# LT3083.net
KiCad netlist of a schematic drawn in Altium Designer
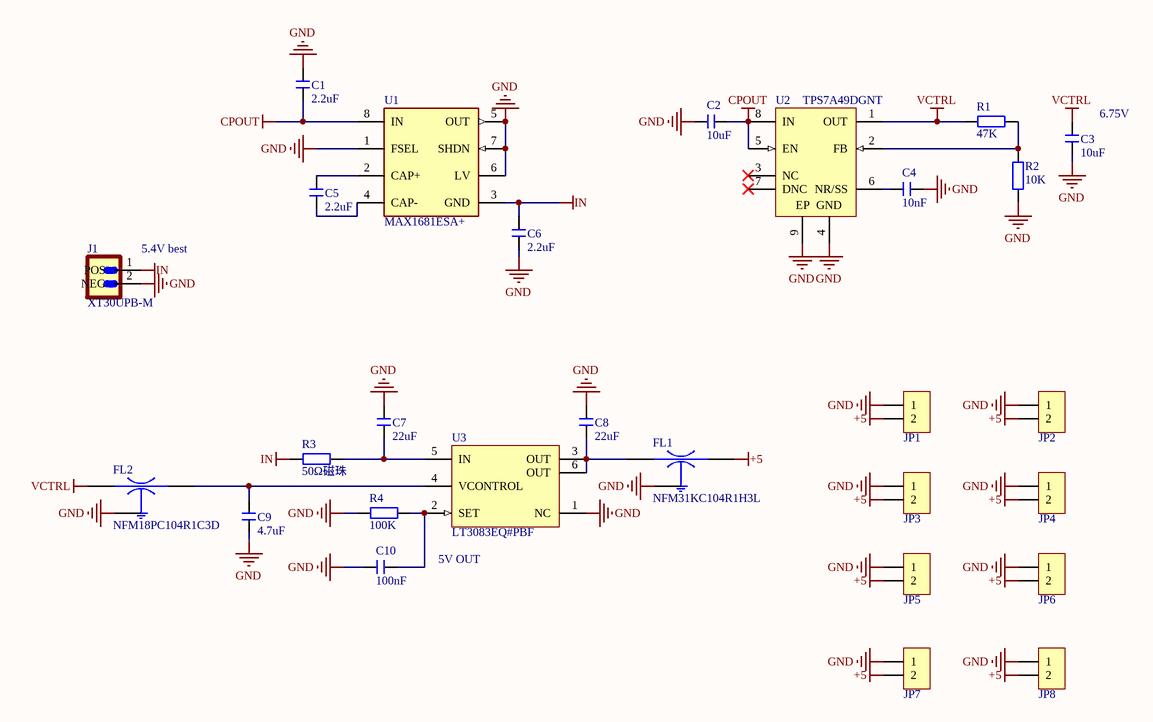
[diagram p0: LT3083.SchDoc]

(export (version "E")
  (design (tool "Eeschema 10.0.6"))
  (components
    (comp (ref "C1")
      (value "2.2uF")
      (footprint "C 0603_L")
      (description "贴片电容")
      (libsource (lib "01 - 电容-电阻-电感") (part "C"))
    )
    (comp (ref "C2")
      (value "10uF")
      (footprint "C 0805_L")
      (description "贴片电容")
      (libsource (lib "01 - 电容-电阻-电感") (part "C"))
    )
    (comp (ref "C3")
      (value "10uF")
      (footprint "C 0805_L")
      (description "贴片电容")
      (libsource (lib "01 - 电容-电阻-电感") (part "C"))
    )
    (comp (ref "C4")
      (value "10nF")
      (footprint "C 0603_L")
      (description "贴片电容")
      (libsource (lib "01 - 电容-电阻-电感") (part "C"))
    )
    (comp (ref "C5")
      (value "2.2uF")
      (footprint "C 0603_L")
      (description "贴片电容")
      (libsource (lib "01 - 电容-电阻-电感") (part "C"))
    )
    (comp (ref "C6")
      (value "2.2uF")
      (footprint "C 0603_L")
      (description "贴片电容")
      (libsource (lib "01 - 电容-电阻-电感") (part "C"))
    )
    (comp (ref "C7")
      (value "22uF")
      (footprint "C 1206_L")
      (description "贴片电容")
      (libsource (lib "01 - 电容-电阻-电感") (part "C"))
    )
    (comp (ref "C8")
      (value "22uF")
      (footprint "C 1206_L")
      (description "贴片电容")
      (libsource (lib "01 - 电容-电阻-电感") (part "C"))
    )
    (comp (ref "C9")
      (value "4.7uF")
      (footprint "C 0603_L")
      (description "贴片电容")
      (libsource (lib "01 - 电容-电阻-电感") (part "C"))
    )
    (comp (ref "C10")
      (value "100nF")
      (footprint "C 0603_L")
      (description "贴片电容")
      (libsource (lib "01 - 电容-电阻-电感") (part "C"))
    )
    (comp (ref "FL1")
      (value "NFM31KC104R1H3L")
      (footprint "FIL_NFM31KC104R1H3L")
      (description "SMD Capacitor with Capacitance: 0.10uF Tol. 20%. Rated Voltage: 50Vdc")
      (fields (field (name "MF") "Murata"))
      (libsource (lib "NFM31KC104R1H3L") (part "NFM31KC104R1H3L"))
    )
    (comp (ref "FL2")
      (value "NFM18PC104R1C3D")
      (footprint "FIL_NFM18PC104R1C3D")
      (description "SMD Capacitor with Capacitance: 0.10uF Tol. 20%. Rated Voltage: 16Vdc")
      (fields (field (name "MF") "Murata") (field (name "DIGI-KEY_PART_NUMBER") "490-6969-1-ND"))
      (libsource (lib "NFM18PC104R1C3D") (part "NFM18PC104R1C3D"))
    )
    (comp (ref "J1")
      (value "XT30UPB-M")
      (footprint "XT30UPB-M")
      (description "Socket; DC supply; XT30; male; PIN: 2; on PCBs; THT; yellow; 15A; 500V")
      (fields (field (name "MF") "amass"))
      (libsource (lib "XT30U") (part "XT30UPB-M"))
    )
    (comp (ref "JP1")
      (value "HDR-1X2")
      (footprint "KF2510-LI-2P")
      (description "2P接插件")
      (libsource (lib "18 - 接插件-脚距2.54mm (100mil) ") (part "Header 2"))
    )
    (comp (ref "JP2")
      (value "HDR-1X2")
      (footprint "KF2510-LI-2P")
      (description "2P接插件")
      (libsource (lib "18 - 接插件-脚距2.54mm (100mil) ") (part "Header 2"))
    )
    (comp (ref "JP3")
      (value "HDR-1X2")
      (footprint "KF2510-LI-2P")
      (description "2P接插件")
      (libsource (lib "18 - 接插件-脚距2.54mm (100mil) ") (part "Header 2"))
    )
    (comp (ref "JP4")
      (value "HDR-1X2")
      (footprint "KF2510-LI-2P")
      (description "2P接插件")
      (libsource (lib "18 - 接插件-脚距2.54mm (100mil) ") (part "Header 2"))
    )
    (comp (ref "JP5")
      (value "HDR-1X2")
      (footprint "KF2510-LI-2P")
      (description "2P接插件")
      (libsource (lib "18 - 接插件-脚距2.54mm (100mil) ") (part "Header 2"))
    )
    (comp (ref "JP6")
      (value "HDR-1X2")
      (footprint "KF2510-LI-2P")
      (description "2P接插件")
      (libsource (lib "18 - 接插件-脚距2.54mm (100mil) ") (part "Header 2"))
    )
    (comp (ref "JP7")
      (value "HDR-1X2")
      (footprint "KF2510-LI-2P")
      (description "2P接插件")
      (libsource (lib "18 - 接插件-脚距2.54mm (100mil) ") (part "Header 2"))
    )
    (comp (ref "JP8")
      (value "HDR-1X2")
      (footprint "KF2510-LI-2P")
      (description "2P接插件")
      (libsource (lib "18 - 接插件-脚距2.54mm (100mil) ") (part "Header 2"))
    )
    (comp (ref "R1")
      (value "47K")
      (footprint "R 0603_L")
      (description "贴片电阻")
      (libsource (lib "01 - 电容-电阻-电感") (part "R"))
    )
    (comp (ref "R2")
      (value "10K")
      (footprint "R 0603_L")
      (description "贴片电阻")
      (libsource (lib "01 - 电容-电阻-电感") (part "R"))
    )
    (comp (ref "R3")
      (value "50Ω磁珠")
      (footprint "R 1206_L")
      (description "贴片电阻")
      (libsource (lib "01 - 电容-电阻-电感") (part "R"))
    )
    (comp (ref "R4")
      (value "100K")
      (footprint "R 0603_L")
      (description "贴片电阻")
      (libsource (lib "01 - 电容-电阻-电感") (part "R"))
    )
    (comp (ref "U1")
      (value "MAX1681ESA+")
      (footprint "FP-S8-5-MFG")
      (description "IC REG CHARGE PUMP INV 8SOIC")
      (fields
        (field (name "MANUFACTURER") "Maxim")
        (field (name "OCTOPART") "https://octopart.com/max1681esa%2B-maxim+integrated-39580721")
      )
      (libsource (lib "MAX1681ESA") (part "MAX1681ESA"))
    )
    (comp (ref "U2")
      (value "TPS7A49DGNT")
      (footprint "DGN0008D_N")
      (fields (field (name "MANUFACTURER") "Texas Instruments") (field (name "PARTNUMBER") "TPS7A4901DGNT"))
      (libsource (lib "TPS7A49") (part "TPS7A49"))
    )
    (comp (ref "U3")
      (value "LT3083EQ#PBF")
      (footprint "LT-Q-5_N")
      (fields (field (name "MANUFACTURER") "Linear Technology"))
      (libsource (lib "LT3083EQ") (part "LT3083EQ"))
    )
  )
  (nets
    (net (code "1") (name "+5") (class "Default")
      (node (ref "FL1") (pin "3") (pinfunction "OUT_3") (pintype "passive"))
      (node (ref "JP1") (pin "2") (pinfunction "2_2") (pintype "passive"))
      (node (ref "JP2") (pin "2") (pinfunction "2_2") (pintype "passive"))
      (node (ref "JP3") (pin "2") (pinfunction "2_2") (pintype "passive"))
      (node (ref "JP4") (pin "2") (pinfunction "2_2") (pintype "passive"))
      (node (ref "JP5") (pin "2") (pinfunction "2_2") (pintype "passive"))
      (node (ref "JP6") (pin "2") (pinfunction "2_2") (pintype "passive"))
      (node (ref "JP7") (pin "2") (pinfunction "2_2") (pintype "passive"))
      (node (ref "JP8") (pin "2") (pinfunction "2_2") (pintype "passive"))
    )
    (net (code "2") (name "CPOUT") (class "Default")
      (node (ref "C1") (pin "1") (pinfunction "1_1") (pintype "passive"))
      (node (ref "C2") (pin "2") (pinfunction "2_2") (pintype "passive"))
      (node (ref "U1") (pin "8") (pinfunction "IN_8") (pintype "power_in"))
      (node (ref "U2") (pin "5") (pinfunction "EN_5") (pintype "input"))
      (node (ref "U2") (pin "8") (pinfunction "IN_8") (pintype "power_in"))
    )
    (net (code "3") (name "GND") (class "Default")
      (node (ref "C1") (pin "2") (pinfunction "2_2") (pintype "passive"))
      (node (ref "C10") (pin "1") (pinfunction "1_1") (pintype "passive"))
      (node (ref "C2") (pin "1") (pinfunction "1_1") (pintype "passive"))
      (node (ref "C3") (pin "2") (pinfunction "2_2") (pintype "passive"))
      (node (ref "C4") (pin "1") (pinfunction "1_1") (pintype "passive"))
      (node (ref "C6") (pin "1") (pinfunction "1_1") (pintype "passive"))
      (node (ref "C7") (pin "2") (pinfunction "2_2") (pintype "passive"))
      (node (ref "C8") (pin "2") (pinfunction "2_2") (pintype "passive"))
      (node (ref "C9") (pin "1") (pinfunction "1_1") (pintype "passive"))
      (node (ref "FL1") (pin "2") (pinfunction "GND_2") (pintype "power_in"))
      (node (ref "FL2") (pin "2") (pinfunction "GND_2") (pintype "power_in"))
      (node (ref "J1") (pin "2") (pinfunction "NEG_2") (pintype "passive"))
      (node (ref "JP1") (pin "1") (pinfunction "1_1") (pintype "passive"))
      (node (ref "JP2") (pin "1") (pinfunction "1_1") (pintype "passive"))
      (node (ref "JP3") (pin "1") (pinfunction "1_1") (pintype "passive"))
      (node (ref "JP4") (pin "1") (pinfunction "1_1") (pintype "passive"))
      (node (ref "JP5") (pin "1") (pinfunction "1_1") (pintype "passive"))
      (node (ref "JP6") (pin "1") (pinfunction "1_1") (pintype "passive"))
      (node (ref "JP7") (pin "1") (pinfunction "1_1") (pintype "passive"))
      (node (ref "JP8") (pin "1") (pinfunction "1_1") (pintype "passive"))
      (node (ref "R2") (pin "2") (pinfunction "2_2") (pintype "passive"))
      (node (ref "R4") (pin "1") (pinfunction "1_1") (pintype "passive"))
      (node (ref "U1") (pin "1") (pinfunction "FSEL_1") (pintype "passive"))
      (node (ref "U1") (pin "5") (pinfunction "OUT_5") (pintype "output"))
      (node (ref "U1") (pin "6") (pinfunction "LV_6") (pintype "passive"))
      (node (ref "U1") (pin "7") (pinfunction "SHDN_7") (pintype "input"))
      (node (ref "U2") (pin "4") (pinfunction "GND_4") (pintype "power_in"))
      (node (ref "U2") (pin "9") (pinfunction "EP_9") (pintype "power_in"))
      (node (ref "U3") (pin "1") (pinfunction "NC_1") (pintype "passive"))
    )
    (net (code "4") (name "IN") (class "Default")
      (node (ref "C6") (pin "2") (pinfunction "2_2") (pintype "passive"))
      (node (ref "J1") (pin "1") (pinfunction "POS_1") (pintype "passive"))
      (node (ref "R3") (pin "1") (pinfunction "1_1") (pintype "passive"))
      (node (ref "U1") (pin "3") (pinfunction "GND_3") (pintype "power_in"))
    )
    (net (code "5") (name "Net-(FL1-IN)") (class "Default")
      (node (ref "C8") (pin "1") (pinfunction "1_1") (pintype "passive"))
      (node (ref "FL1") (pin "1") (pinfunction "IN_1") (pintype "passive"))
      (node (ref "U3") (pin "3") (pinfunction "OUT_3") (pintype "power_in"))
      (node (ref "U3") (pin "6") (pinfunction "OUT_6") (pintype "power_in"))
    )
    (net (code "6") (name "Net-(FL2-OUT)") (class "Default")
      (node (ref "C9") (pin "2") (pinfunction "2_2") (pintype "passive"))
      (node (ref "FL2") (pin "3") (pinfunction "OUT_3") (pintype "passive"))
      (node (ref "U3") (pin "4") (pinfunction "VCONTROL_4") (pintype "power_in"))
    )
    (net (code "7") (name "Net-(U1-CAP+)") (class "Default")
      (node (ref "C5") (pin "2") (pinfunction "2_2") (pintype "passive"))
      (node (ref "U1") (pin "2") (pinfunction "CAP+_2") (pintype "passive"))
    )
    (net (code "8") (name "Net-(U1-CAP-)") (class "Default")
      (node (ref "C5") (pin "1") (pinfunction "1_1") (pintype "passive"))
      (node (ref "U1") (pin "4") (pinfunction "CAP-_4") (pintype "passive"))
    )
    (net (code "9") (name "Net-(U2-FB)") (class "Default")
      (node (ref "R1") (pin "1") (pinfunction "1_1") (pintype "passive"))
      (node (ref "R2") (pin "1") (pinfunction "1_1") (pintype "passive"))
      (node (ref "U2") (pin "2") (pinfunction "FB_2") (pintype "input"))
    )
    (net (code "10") (name "Net-(U2-NR{slash}SS)") (class "Default")
      (node (ref "C4") (pin "2") (pinfunction "2_2") (pintype "passive"))
      (node (ref "U2") (pin "6") (pinfunction "NR/SS_6") (pintype "passive"))
    )
    (net (code "11") (name "Net-(U3-IN)") (class "Default")
      (node (ref "C7") (pin "1") (pinfunction "1_1") (pintype "passive"))
      (node (ref "R3") (pin "2") (pinfunction "2_2") (pintype "passive"))
      (node (ref "U3") (pin "5") (pinfunction "IN_5") (pintype "power_in"))
    )
    (net (code "12") (name "Net-(U3-SET)") (class "Default")
      (node (ref "C10") (pin "2") (pinfunction "2_2") (pintype "passive"))
      (node (ref "R4") (pin "2") (pinfunction "2_2") (pintype "passive"))
      (node (ref "U3") (pin "2") (pinfunction "SET_2") (pintype "input"))
    )
    (net (code "13") (name "VCTRL") (class "Default")
      (node (ref "C3") (pin "1") (pinfunction "1_1") (pintype "passive"))
      (node (ref "FL2") (pin "1") (pinfunction "IN_1") (pintype "passive"))
      (node (ref "R1") (pin "2") (pinfunction "2_2") (pintype "passive"))
      (node (ref "U2") (pin "1") (pinfunction "OUT_1") (pintype "power_in"))
    )
    (net (code "14") (name "unconnected-(U2-DNC-Pad7)") (class "Default")
      (node (ref "U2") (pin "7") (pinfunction "DNC_7") (pintype "passive+no_connect"))
    )
    (net (code "15") (name "unconnected-(U2-NC-Pad3)") (class "Default")
      (node (ref "U2") (pin "3") (pinfunction "NC_3") (pintype "passive+no_connect"))
    )
  )
)
